# brush_motor_pcb_v1_1.net
KiCad netlist of a schematic drawn in EAGLE
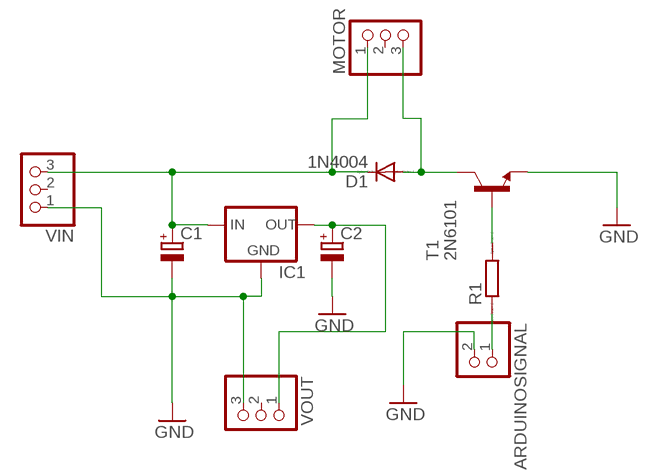
[diagram p0: schematic, sheet 1]

(export (version "E")
  (design (tool "Eeschema 10.0.6"))
  (components
    (comp (ref "ARDUINOSIGNAL")
      (value "PINHD-1X2")
      (footprint "eagle-import:1X02")
      (libsource (lib "eagle-import") (part "PINHD-1X2"))
    )
    (comp (ref "C1")
      (value "CPOL-EUE2.5-6")
      (footprint "eagle-import:E2,5-6")
      (libsource (lib "eagle-import") (part "CPOL-EUE2.5-6"))
    )
    (comp (ref "C2")
      (value "CPOL-EUE2.5-6")
      (footprint "eagle-import:E2,5-6")
      (libsource (lib "eagle-import") (part "CPOL-EUE2.5-6"))
    )
    (comp (ref "D1")
      (value "1N4004")
      (footprint "eagle-import:DO41-10")
      (libsource (lib "eagle-import") (part "1N4004"))
    )
    (comp (ref "IC1")
      (value "78XXS")
      (footprint "eagle-import:78XXS")
      (libsource (lib "eagle-import") (part "78XXS"))
    )
    (comp (ref "MOTOR")
      (value "PINHD-1X3")
      (footprint "eagle-import:1X03")
      (libsource (lib "eagle-import") (part "PINHD-1X3"))
    )
    (comp (ref "R1")
      (value "R0207/10")
      (footprint "eagle-import:0207_10")
      (libsource (lib "eagle-import") (part "R0207/10"))
    )
    (comp (ref "T1")
      (value "2N6101")
      (footprint "eagle-import:TO220")
      (libsource (lib "eagle-import") (part "2N6101"))
    )
    (comp (ref "VIN")
      (value "PINHD-1X3")
      (footprint "eagle-import:1X03")
      (libsource (lib "eagle-import") (part "PINHD-1X3"))
    )
    (comp (ref "VOUT")
      (value "PINHD-1X3")
      (footprint "eagle-import:1X03")
      (libsource (lib "eagle-import") (part "PINHD-1X3"))
    )
  )
  (nets
    (net (code "1") (name "GND") (class "Default")
      (node (ref "ARDUINOSIGNAL") (pin "2") (pinfunction "2_2") (pintype "passive"))
      (node (ref "C1") (pin "-") (pinfunction "-_-") (pintype "passive"))
      (node (ref "C2") (pin "-") (pinfunction "-_-") (pintype "passive"))
      (node (ref "IC1") (pin "GND") (pinfunction "GND_GND") (pintype "input"))
      (node (ref "T1") (pin "3") (pinfunction "E_3") (pintype "passive"))
      (node (ref "VIN") (pin "1") (pinfunction "1_1") (pintype "passive"))
      (node (ref "VOUT") (pin "3") (pinfunction "3_3") (pintype "passive"))
    )
    (net (code "2") (name "Net-(ARDUINOSIGNAL-Pad1)") (class "Default")
      (node (ref "ARDUINOSIGNAL") (pin "1") (pinfunction "1_1") (pintype "passive"))
      (node (ref "R1") (pin "1") (pinfunction "1_1") (pintype "passive"))
    )
    (net (code "3") (name "Net-(C1-Pad+)") (class "Default")
      (node (ref "C1") (pin "+") (pinfunction "+_+") (pintype "passive"))
      (node (ref "D1") (pin "C") (pinfunction "C_C") (pintype "passive"))
      (node (ref "IC1") (pin "IN") (pinfunction "IN_IN") (pintype "input"))
      (node (ref "MOTOR") (pin "1") (pinfunction "1_1") (pintype "passive"))
      (node (ref "VIN") (pin "3") (pinfunction "3_3") (pintype "passive"))
    )
    (net (code "4") (name "Net-(C2-Pad+)") (class "Default")
      (node (ref "C2") (pin "+") (pinfunction "+_+") (pintype "passive"))
      (node (ref "IC1") (pin "OUT") (pinfunction "OUT_OUT") (pintype "passive"))
      (node (ref "VOUT") (pin "1") (pinfunction "1_1") (pintype "passive"))
    )
    (net (code "5") (name "Net-(T1-B)") (class "Default")
      (node (ref "R1") (pin "2") (pinfunction "2_2") (pintype "passive"))
      (node (ref "T1") (pin "1") (pinfunction "B_1") (pintype "passive"))
    )
    (net (code "6") (name "Net-(T1-C)") (class "Default")
      (node (ref "D1") (pin "A") (pinfunction "A_A") (pintype "passive"))
      (node (ref "MOTOR") (pin "3") (pinfunction "3_3") (pintype "passive"))
      (node (ref "T1") (pin "2") (pinfunction "C_2") (pintype "passive"))
    )
    (net (code "7") (name "unconnected-(MOTOR-Pad2)") (class "Default")
      (node (ref "MOTOR") (pin "2") (pinfunction "2_2") (pintype "passive"))
    )
    (net (code "8") (name "unconnected-(VIN-Pad2)") (class "Default")
      (node (ref "VIN") (pin "2") (pinfunction "2_2") (pintype "passive"))
    )
    (net (code "9") (name "unconnected-(VOUT-Pad2)") (class "Default")
      (node (ref "VOUT") (pin "2") (pinfunction "2_2") (pintype "passive"))
    )
  )
)
